# Nose_IR_emitter_1_2.net
KiCad netlist of a schematic drawn in EAGLE
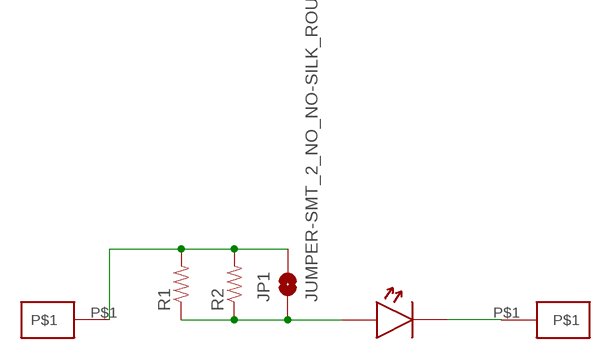
[diagram p0: schematic, sheet 1]

(export (version "E")
  (design (tool "Eeschema 10.0.6"))
  (components
    (comp (ref "JP1")
      (value "JUMPER-SMT_2_NO_NO-SILK_ROUND")
      (footprint "eagle-import:SMT-JUMPER_2_NO_NO-SILK_ROUND")
      (libsource (lib "eagle-import") (part "JUMPER-SMT_2_NO_NO-SILK_ROUND"))
    )
    (comp (ref "R1")
      (value "RESISTOR0805-RES")
      (footprint "eagle-import:0805")
      (libsource (lib "eagle-import") (part "RESISTOR0805-RES"))
    )
    (comp (ref "R2")
      (value "RESISTOR0805-RES")
      (footprint "eagle-import:0805")
      (libsource (lib "eagle-import") (part "RESISTOR0805-RES"))
    )
    (comp (ref "U$1")
      (value "IR_EMITTER")
      (footprint "eagle-import:IR_EMITTER")
      (libsource (lib "eagle-import") (part "IR_EMITTER"))
    )
    (comp (ref "U$2")
      (value "PAD")
      (footprint "eagle-import:PAD")
      (libsource (lib "eagle-import") (part "PAD"))
    )
    (comp (ref "U$3")
      (value "PAD")
      (footprint "eagle-import:PAD")
      (libsource (lib "eagle-import") (part "PAD"))
    )
  )
  (nets
    (net (code "1") (name "Net-(JP1-Pad1)") (class "Default")
      (node (ref "JP1") (pin "1") (pinfunction "1_1") (pintype "passive"))
      (node (ref "R1") (pin "1") (pinfunction "1_1") (pintype "passive"))
      (node (ref "R2") (pin "1") (pinfunction "1_1") (pintype "passive"))
      (node (ref "U$1") (pin "ANODE") (pinfunction "ANODE_ANODE") (pintype "bidirectional"))
    )
    (net (code "2") (name "Net-(JP1-Pad2)") (class "Default")
      (node (ref "JP1") (pin "2") (pinfunction "2_2") (pintype "passive"))
      (node (ref "R1") (pin "2") (pinfunction "2_2") (pintype "passive"))
      (node (ref "R2") (pin "2") (pinfunction "2_2") (pintype "passive"))
      (node (ref "U$2") (pin "P$1") (pinfunction "P$1_P$1") (pintype "bidirectional"))
    )
    (net (code "3") (name "Net-(U$1-PadCATHODE)") (class "Default")
      (node (ref "U$1") (pin "CATHODE") (pinfunction "CATHODE_CATHODE") (pintype "bidirectional"))
      (node (ref "U$3") (pin "P$1") (pinfunction "P$1_P$1") (pintype "bidirectional"))
    )
  )
)
